# RJ45_Adapter.net
KiCad netlist of a schematic drawn in EAGLE
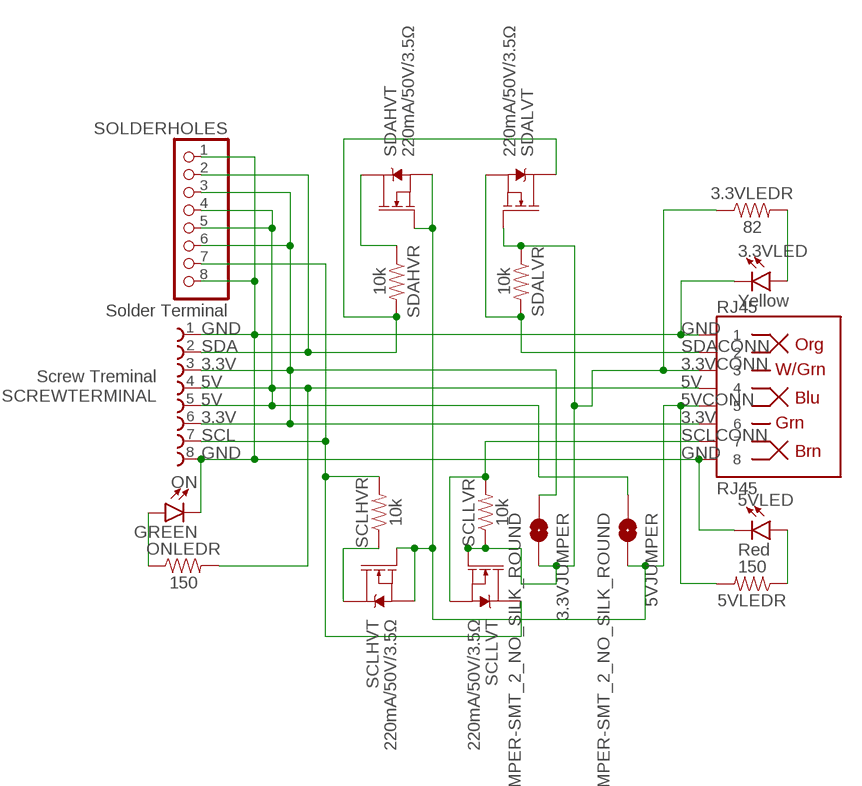
[diagram p0: schematic, sheet 1]

(export (version "E")
  (design (tool "Eeschema 10.0.6"))
  (components
    (comp (ref "3.3VJUMPER")
      (value "JUMPER-SMT_2_NO_SILK_ROUND")
      (footprint "eagle-import:SMT-JUMPER_2_NO_SILK_ROUND")
      (libsource (lib "eagle-import") (part "JUMPER-SMT_2_NO_SILK_ROUND"))
    )
    (comp (ref "3.3VLED")
      (value "Yellow")
      (footprint "eagle-import:LED-0603")
      (libsource (lib "eagle-import") (part "LED-YELLOW0603-SMART"))
    )
    (comp (ref "3.3VLEDR")
      (value "82")
      (footprint "eagle-import:0603")
      (libsource (lib "eagle-import") (part "82OHM-0603-1/10W-1%"))
    )
    (comp (ref "5VJUMPER")
      (value "JUMPER-SMT_2_NO_SILK_ROUND")
      (footprint "eagle-import:SMT-JUMPER_2_NO_SILK_ROUND")
      (libsource (lib "eagle-import") (part "JUMPER-SMT_2_NO_SILK_ROUND"))
    )
    (comp (ref "5VLED")
      (value "Red")
      (footprint "eagle-import:LED-0603")
      (libsource (lib "eagle-import") (part "LED-RED0603-SMART"))
    )
    (comp (ref "5VLEDR")
      (value "150")
      (footprint "eagle-import:0603")
      (libsource (lib "eagle-import") (part "150OHM-0603-1/10W-1%"))
    )
    (comp (ref "ON")
      (value "GREEN")
      (footprint "eagle-import:LED-0603")
      (libsource (lib "eagle-import") (part "LED-GREEN0603"))
    )
    (comp (ref "ONLEDR")
      (value "150")
      (footprint "eagle-import:0603")
      (libsource (lib "eagle-import") (part "150OHM-0603-1/10W-1%"))
    )
    (comp (ref "RJ45")
      (value "RJ45")
      (footprint "eagle-import:RJ45-8")
      (libsource (lib "eagle-import") (part "RJ45-8"))
    )
    (comp (ref "SCLHVR")
      (value "10k")
      (footprint "eagle-import:0603")
      (libsource (lib "eagle-import") (part "10KOHM-0603-1/10W-1%"))
    )
    (comp (ref "SCLHVT")
      (value "220mA/50V/3.5Ω")
      (footprint "eagle-import:SOT23-3")
      (libsource (lib "eagle-import") (part "MOSFET-NCH-BSS138"))
    )
    (comp (ref "SCLLVR")
      (value "10k")
      (footprint "eagle-import:0603")
      (libsource (lib "eagle-import") (part "10KOHM-0603-1/10W-1%"))
    )
    (comp (ref "SCLLVT")
      (value "220mA/50V/3.5Ω")
      (footprint "eagle-import:SOT23-3")
      (libsource (lib "eagle-import") (part "MOSFET-NCH-BSS138"))
    )
    (comp (ref "SCREWTERMINAL")
      (value "Screw Treminal")
      (footprint "eagle-import:691243300008")
      (libsource (lib "eagle-import") (part "691243300008"))
    )
    (comp (ref "SDAHVR")
      (value "10k")
      (footprint "eagle-import:0603")
      (libsource (lib "eagle-import") (part "10KOHM-0603-1/10W-1%"))
    )
    (comp (ref "SDAHVT")
      (value "220mA/50V/3.5Ω")
      (footprint "eagle-import:SOT23-3")
      (libsource (lib "eagle-import") (part "MOSFET-NCH-BSS138"))
    )
    (comp (ref "SDALVR")
      (value "10k")
      (footprint "eagle-import:0603")
      (libsource (lib "eagle-import") (part "10KOHM-0603-1/10W-1%"))
    )
    (comp (ref "SDALVT")
      (value "220mA/50V/3.5Ω")
      (footprint "eagle-import:SOT23-3")
      (libsource (lib "eagle-import") (part "MOSFET-NCH-BSS138"))
    )
    (comp (ref "SOLDERHOLES")
      (value "Solder Terminal")
      (footprint "eagle-import:1X08-3.5MM")
      (libsource (lib "eagle-import") (part "PINHD-1X8-3.5MM"))
    )
  )
  (nets
    (net (code "1") (name "/3.3V") (class "Default")
      (node (ref "3.3VJUMPER") (pin "1") (pinfunction "1_1") (pintype "passive"))
      (node (ref "RJ45") (pin "6") (pinfunction "6_6") (pintype "bidirectional"))
      (node (ref "SCREWTERMINAL") (pin "3") (pinfunction "6_3") (pintype "passive"))
      (node (ref "SCREWTERMINAL") (pin "6") (pinfunction "3_6") (pintype "passive"))
      (node (ref "SOLDERHOLES") (pin "3") (pinfunction "3_3") (pintype "passive"))
      (node (ref "SOLDERHOLES") (pin "6") (pinfunction "6_6") (pintype "passive"))
    )
    (net (code "2") (name "/3.3VCONN") (class "Default")
      (node (ref "3.3VJUMPER") (pin "2") (pinfunction "2_2") (pintype "passive"))
      (node (ref "3.3VLEDR") (pin "1") (pinfunction "1_1") (pintype "passive"))
      (node (ref "RJ45") (pin "3") (pinfunction "3_3") (pintype "bidirectional"))
      (node (ref "SCLLVR") (pin "1") (pinfunction "1_1") (pintype "passive"))
      (node (ref "SCLLVT") (pin "1") (pinfunction "G_1") (pintype "bidirectional"))
      (node (ref "SDALVR") (pin "1") (pinfunction "1_1") (pintype "passive"))
      (node (ref "SDALVT") (pin "1") (pinfunction "G_1") (pintype "bidirectional"))
    )
    (net (code "3") (name "/5V") (class "Default")
      (node (ref "5VJUMPER") (pin "1") (pinfunction "1_1") (pintype "passive"))
      (node (ref "ONLEDR") (pin "2") (pinfunction "2_2") (pintype "passive"))
      (node (ref "RJ45") (pin "4") (pinfunction "4_4") (pintype "bidirectional"))
      (node (ref "SCREWTERMINAL") (pin "4") (pinfunction "5_4") (pintype "passive"))
      (node (ref "SCREWTERMINAL") (pin "5") (pinfunction "4_5") (pintype "passive"))
      (node (ref "SOLDERHOLES") (pin "4") (pinfunction "4_4") (pintype "passive"))
      (node (ref "SOLDERHOLES") (pin "5") (pinfunction "5_5") (pintype "passive"))
    )
    (net (code "4") (name "/5VCONN") (class "Default")
      (node (ref "5VJUMPER") (pin "2") (pinfunction "2_2") (pintype "passive"))
      (node (ref "5VLEDR") (pin "2") (pinfunction "2_2") (pintype "passive"))
      (node (ref "RJ45") (pin "5") (pinfunction "5_5") (pintype "bidirectional"))
      (node (ref "SCLHVT") (pin "1") (pinfunction "G_1") (pintype "bidirectional"))
      (node (ref "SCLHVT") (pin "2") (pinfunction "S_2") (pintype "bidirectional"))
      (node (ref "SDAHVT") (pin "1") (pinfunction "G_1") (pintype "bidirectional"))
      (node (ref "SDAHVT") (pin "2") (pinfunction "S_2") (pintype "bidirectional"))
    )
    (net (code "5") (name "/GND") (class "Default")
      (node (ref "3.3VLED") (pin "C") (pinfunction "C_C") (pintype "passive"))
      (node (ref "5VLED") (pin "C") (pinfunction "C_C") (pintype "passive"))
      (node (ref "ON") (pin "C") (pinfunction "C_C") (pintype "passive"))
      (node (ref "RJ45") (pin "1") (pinfunction "1_1") (pintype "bidirectional"))
      (node (ref "RJ45") (pin "8") (pinfunction "8_8") (pintype "bidirectional"))
      (node (ref "SCREWTERMINAL") (pin "1") (pinfunction "8_1") (pintype "passive"))
      (node (ref "SCREWTERMINAL") (pin "8") (pinfunction "1_8") (pintype "passive"))
      (node (ref "SOLDERHOLES") (pin "1") (pinfunction "1_1") (pintype "passive"))
      (node (ref "SOLDERHOLES") (pin "8") (pinfunction "8_8") (pintype "passive"))
    )
    (net (code "6") (name "/SCL") (class "Default")
      (node (ref "SCLHVR") (pin "2") (pinfunction "2_2") (pintype "passive"))
      (node (ref "SCLLVT") (pin "3") (pinfunction "D_3") (pintype "bidirectional"))
      (node (ref "SCREWTERMINAL") (pin "7") (pinfunction "2_7") (pintype "passive"))
      (node (ref "SOLDERHOLES") (pin "7") (pinfunction "7_7") (pintype "passive"))
    )
    (net (code "7") (name "/SCLCONN") (class "Default")
      (node (ref "RJ45") (pin "7") (pinfunction "7_7") (pintype "bidirectional"))
      (node (ref "SCLLVR") (pin "2") (pinfunction "2_2") (pintype "passive"))
      (node (ref "SCLLVT") (pin "2") (pinfunction "S_2") (pintype "bidirectional"))
    )
    (net (code "8") (name "/SDA") (class "Default")
      (node (ref "SCREWTERMINAL") (pin "2") (pinfunction "7_2") (pintype "passive"))
      (node (ref "SDAHVR") (pin "2") (pinfunction "2_2") (pintype "passive"))
      (node (ref "SDALVT") (pin "3") (pinfunction "D_3") (pintype "bidirectional"))
      (node (ref "SOLDERHOLES") (pin "2") (pinfunction "2_2") (pintype "passive"))
    )
    (net (code "9") (name "/SDACONN") (class "Default")
      (node (ref "RJ45") (pin "2") (pinfunction "2_2") (pintype "bidirectional"))
      (node (ref "SDALVR") (pin "2") (pinfunction "2_2") (pintype "passive"))
      (node (ref "SDALVT") (pin "2") (pinfunction "S_2") (pintype "bidirectional"))
    )
    (net (code "10") (name "Net-(3.3VLED-PadA)") (class "Default")
      (node (ref "3.3VLED") (pin "A") (pinfunction "A_A") (pintype "passive"))
      (node (ref "3.3VLEDR") (pin "2") (pinfunction "2_2") (pintype "passive"))
    )
    (net (code "11") (name "Net-(5VLED-PadA)") (class "Default")
      (node (ref "5VLED") (pin "A") (pinfunction "A_A") (pintype "passive"))
      (node (ref "5VLEDR") (pin "1") (pinfunction "1_1") (pintype "passive"))
    )
    (net (code "12") (name "Net-(ON-PadA)") (class "Default")
      (node (ref "ON") (pin "A") (pinfunction "A_A") (pintype "passive"))
      (node (ref "ONLEDR") (pin "1") (pinfunction "1_1") (pintype "passive"))
    )
    (net (code "13") (name "Net-(SCLHVT-D)") (class "Default")
      (node (ref "SCLHVR") (pin "1") (pinfunction "1_1") (pintype "passive"))
      (node (ref "SCLHVT") (pin "3") (pinfunction "D_3") (pintype "bidirectional"))
    )
    (net (code "14") (name "Net-(SDAHVT-D)") (class "Default")
      (node (ref "SDAHVR") (pin "1") (pinfunction "1_1") (pintype "passive"))
      (node (ref "SDAHVT") (pin "3") (pinfunction "D_3") (pintype "bidirectional"))
    )
  )
)
